# Main.net
KiCad netlist of a schematic drawn in Altium Designer
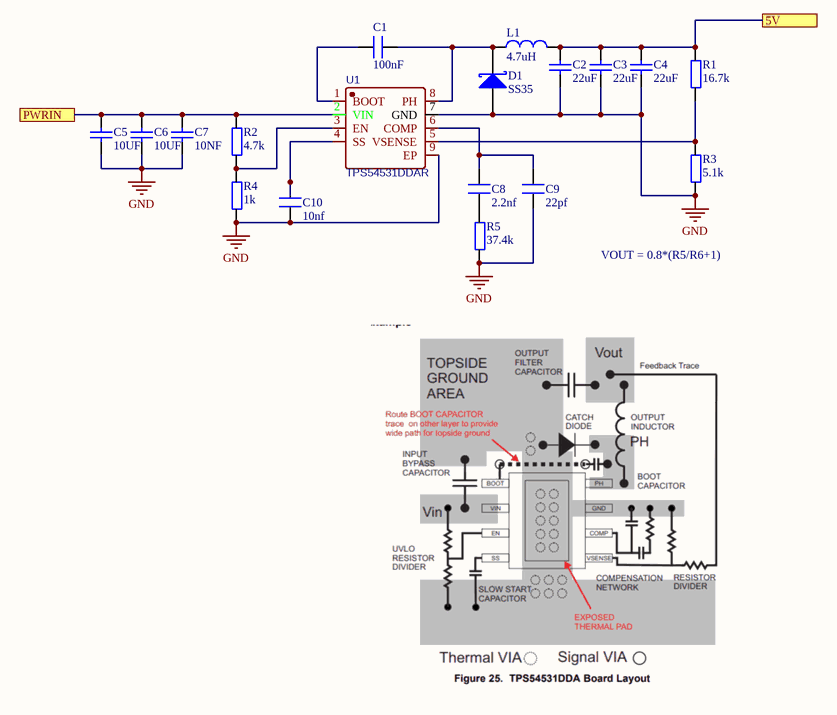
[diagram p0: Main.SchDoc]

(export (version "E")
  (design (tool "Eeschema 10.0.6"))
  (components
    (comp (ref "C1")
      (value "100nF")
      (footprint "C 0603")
      (libsource (lib "IMX6UL_ALPHA(底板)_V2.0") (part "C"))
    )
    (comp (ref "C2")
      (value "22uF")
      (footprint "1206-C")
      (description "陶瓷电容")
      (libsource (lib "我的原理图库") (part "CAP"))
    )
    (comp (ref "C3")
      (value "22uF")
      (footprint "1206-C")
      (description "陶瓷电容")
      (libsource (lib "我的原理图库") (part "CAP"))
    )
    (comp (ref "C4")
      (value "22uF")
      (footprint "1206-C")
      (description "陶瓷电容")
      (libsource (lib "我的原理图库") (part "CAP"))
    )
    (comp (ref "C5")
      (value "10UF")
      (footprint "1206-C")
      (description "陶瓷电容")
      (libsource (lib "我的原理图库") (part "CAP"))
    )
    (comp (ref "C6")
      (value "10UF")
      (footprint "1206-C")
      (description "陶瓷电容")
      (libsource (lib "我的原理图库") (part "CAP"))
    )
    (comp (ref "C7")
      (value "10NF")
      (footprint "1206-C")
      (description "陶瓷电容")
      (libsource (lib "我的原理图库") (part "CAP"))
    )
    (comp (ref "C8")
      (value "2.2nf")
      (footprint "C 0603")
      (libsource (lib "IMX6UL_ALPHA(底板)_V2.0") (part "C"))
    )
    (comp (ref "C9") (value "22pf") (footprint "C 0603") (libsource (lib "IMX6UL_ALPHA(底板)_V2.0") (part "C")))
    (comp (ref "C10")
      (value "10nf")
      (footprint "C 0603")
      (libsource (lib "IMX6UL_ALPHA(底板)_V2.0") (part "C"))
    )
    (comp (ref "D1")
      (value "SS35")
      (footprint "SMC_L6.9-W5.9-LS7.9-RD")
      (description "Schottky Diode")
      (fields (field (name "PUBLISHER") "Altium Limited"))
      (libsource (lib "我的原理图库") (part "D Schottky"))
    )
    (comp (ref "L1")
      (value "4.7uH")
      (footprint "L-CDRH74R")
      (description "贴片屏蔽电感")
      (libsource (lib "Miscellaneous Base") (part "INDUCTOR-SMD"))
    )
    (comp (ref "R1")
      (value "16.7k")
      (footprint "R 0603")
      (libsource (lib "IMX6UL_ALPHA(底板)_V2.0") (part "R"))
    )
    (comp (ref "R2") (value "4.7k") (footprint "R 0603") (libsource (lib "IMX6UL_ALPHA(底板)_V2.0") (part "R")))
    (comp (ref "R3") (value "5.1k") (footprint "R 0603") (libsource (lib "IMX6UL_ALPHA(底板)_V2.0") (part "R")))
    (comp (ref "R4") (value "1k") (footprint "R 0603") (libsource (lib "IMX6UL_ALPHA(底板)_V2.0") (part "R")))
    (comp (ref "R5")
      (value "37.4k")
      (footprint "R 0603")
      (libsource (lib "IMX6UL_ALPHA(底板)_V2.0") (part "R"))
    )
    (comp (ref "U1")
      (value "TPS54531DDAR")
      (footprint "SOIC-8_L5.0-W4.0-P1.27-LS6.0-BL-EP")
      (fields
        (field (name "BOM_MANUFACTURER PART") "TPS79333DBVR")
        (field (name "BOM_SUPPLIER PART") "C9840")
      )
      (libsource (lib "我的原理图库") (part "TPS54531DDAR"))
    )
  )
  (nets
    (net (code "1") (name "/5V") (class "Default")
      (node (ref "C2") (pin "2") (pinfunction "2_2") (pintype "passive"))
      (node (ref "C3") (pin "2") (pinfunction "2_2") (pintype "passive"))
      (node (ref "C4") (pin "2") (pinfunction "2_2") (pintype "passive"))
      (node (ref "L1") (pin "2") (pinfunction "2_2") (pintype "passive"))
      (node (ref "R1") (pin "2") (pintype "passive"))
    )
    (net (code "2") (name "/PWRIN") (class "Default")
      (node (ref "C5") (pin "2") (pinfunction "2_2") (pintype "passive"))
      (node (ref "C6") (pin "2") (pinfunction "2_2") (pintype "passive"))
      (node (ref "C7") (pin "2") (pinfunction "2_2") (pintype "passive"))
      (node (ref "R2") (pin "2") (pintype "passive"))
      (node (ref "U1") (pin "2") (pinfunction "VIN_2") (pintype "passive"))
    )
    (net (code "3") (name "GND") (class "Default")
      (node (ref "C10") (pin "1") (pintype "passive"))
      (node (ref "C2") (pin "1") (pinfunction "1_1") (pintype "passive"))
      (node (ref "C3") (pin "1") (pinfunction "1_1") (pintype "passive"))
      (node (ref "C4") (pin "1") (pinfunction "1_1") (pintype "passive"))
      (node (ref "C5") (pin "1") (pinfunction "1_1") (pintype "passive"))
      (node (ref "C6") (pin "1") (pinfunction "1_1") (pintype "passive"))
      (node (ref "C7") (pin "1") (pinfunction "1_1") (pintype "passive"))
      (node (ref "C9") (pin "1") (pintype "passive"))
      (node (ref "D1") (pin "1") (pinfunction "A_1") (pintype "passive"))
      (node (ref "R3") (pin "1") (pintype "passive"))
      (node (ref "R4") (pin "1") (pintype "passive"))
      (node (ref "R5") (pin "1") (pintype "passive"))
      (node (ref "U1") (pin "7") (pinfunction "GND_7") (pintype "passive"))
      (node (ref "U1") (pin "9") (pinfunction "EP_9") (pintype "passive"))
    )
    (net (code "4") (name "Net-(C8-Pad1)") (class "Default")
      (node (ref "C8") (pin "1") (pintype "passive"))
      (node (ref "R5") (pin "2") (pintype "passive"))
    )
    (net (code "5") (name "Net-(D1-K)") (class "Default")
      (node (ref "C1") (pin "1") (pintype "passive"))
      (node (ref "D1") (pin "2") (pinfunction "K_2") (pintype "passive"))
      (node (ref "L1") (pin "1") (pinfunction "1_1") (pintype "passive"))
      (node (ref "U1") (pin "8") (pinfunction "PH_8") (pintype "passive"))
    )
    (net (code "6") (name "Net-(U1-BOOT)") (class "Default")
      (node (ref "C1") (pin "2") (pintype "passive"))
      (node (ref "U1") (pin "1") (pinfunction "BOOT_1") (pintype "passive"))
    )
    (net (code "7") (name "Net-(U1-COMP)") (class "Default")
      (node (ref "C8") (pin "2") (pintype "passive"))
      (node (ref "C9") (pin "2") (pintype "passive"))
      (node (ref "U1") (pin "6") (pinfunction "COMP_6") (pintype "passive"))
    )
    (net (code "8") (name "Net-(U1-EN)") (class "Default")
      (node (ref "R2") (pin "1") (pintype "passive"))
      (node (ref "R4") (pin "2") (pintype "passive"))
      (node (ref "U1") (pin "3") (pinfunction "EN_3") (pintype "passive"))
    )
    (net (code "9") (name "Net-(U1-SS)") (class "Default")
      (node (ref "C10") (pin "2") (pintype "passive"))
      (node (ref "U1") (pin "4") (pinfunction "SS_4") (pintype "passive"))
    )
    (net (code "10") (name "Net-(U1-VSENSE)") (class "Default")
      (node (ref "R1") (pin "1") (pintype "passive"))
      (node (ref "R3") (pin "2") (pintype "passive"))
      (node (ref "U1") (pin "5") (pinfunction "VSENSE_5") (pintype "passive"))
    )
  )
)
